# H-Bridge.net
KiCad netlist of a schematic drawn in EAGLE
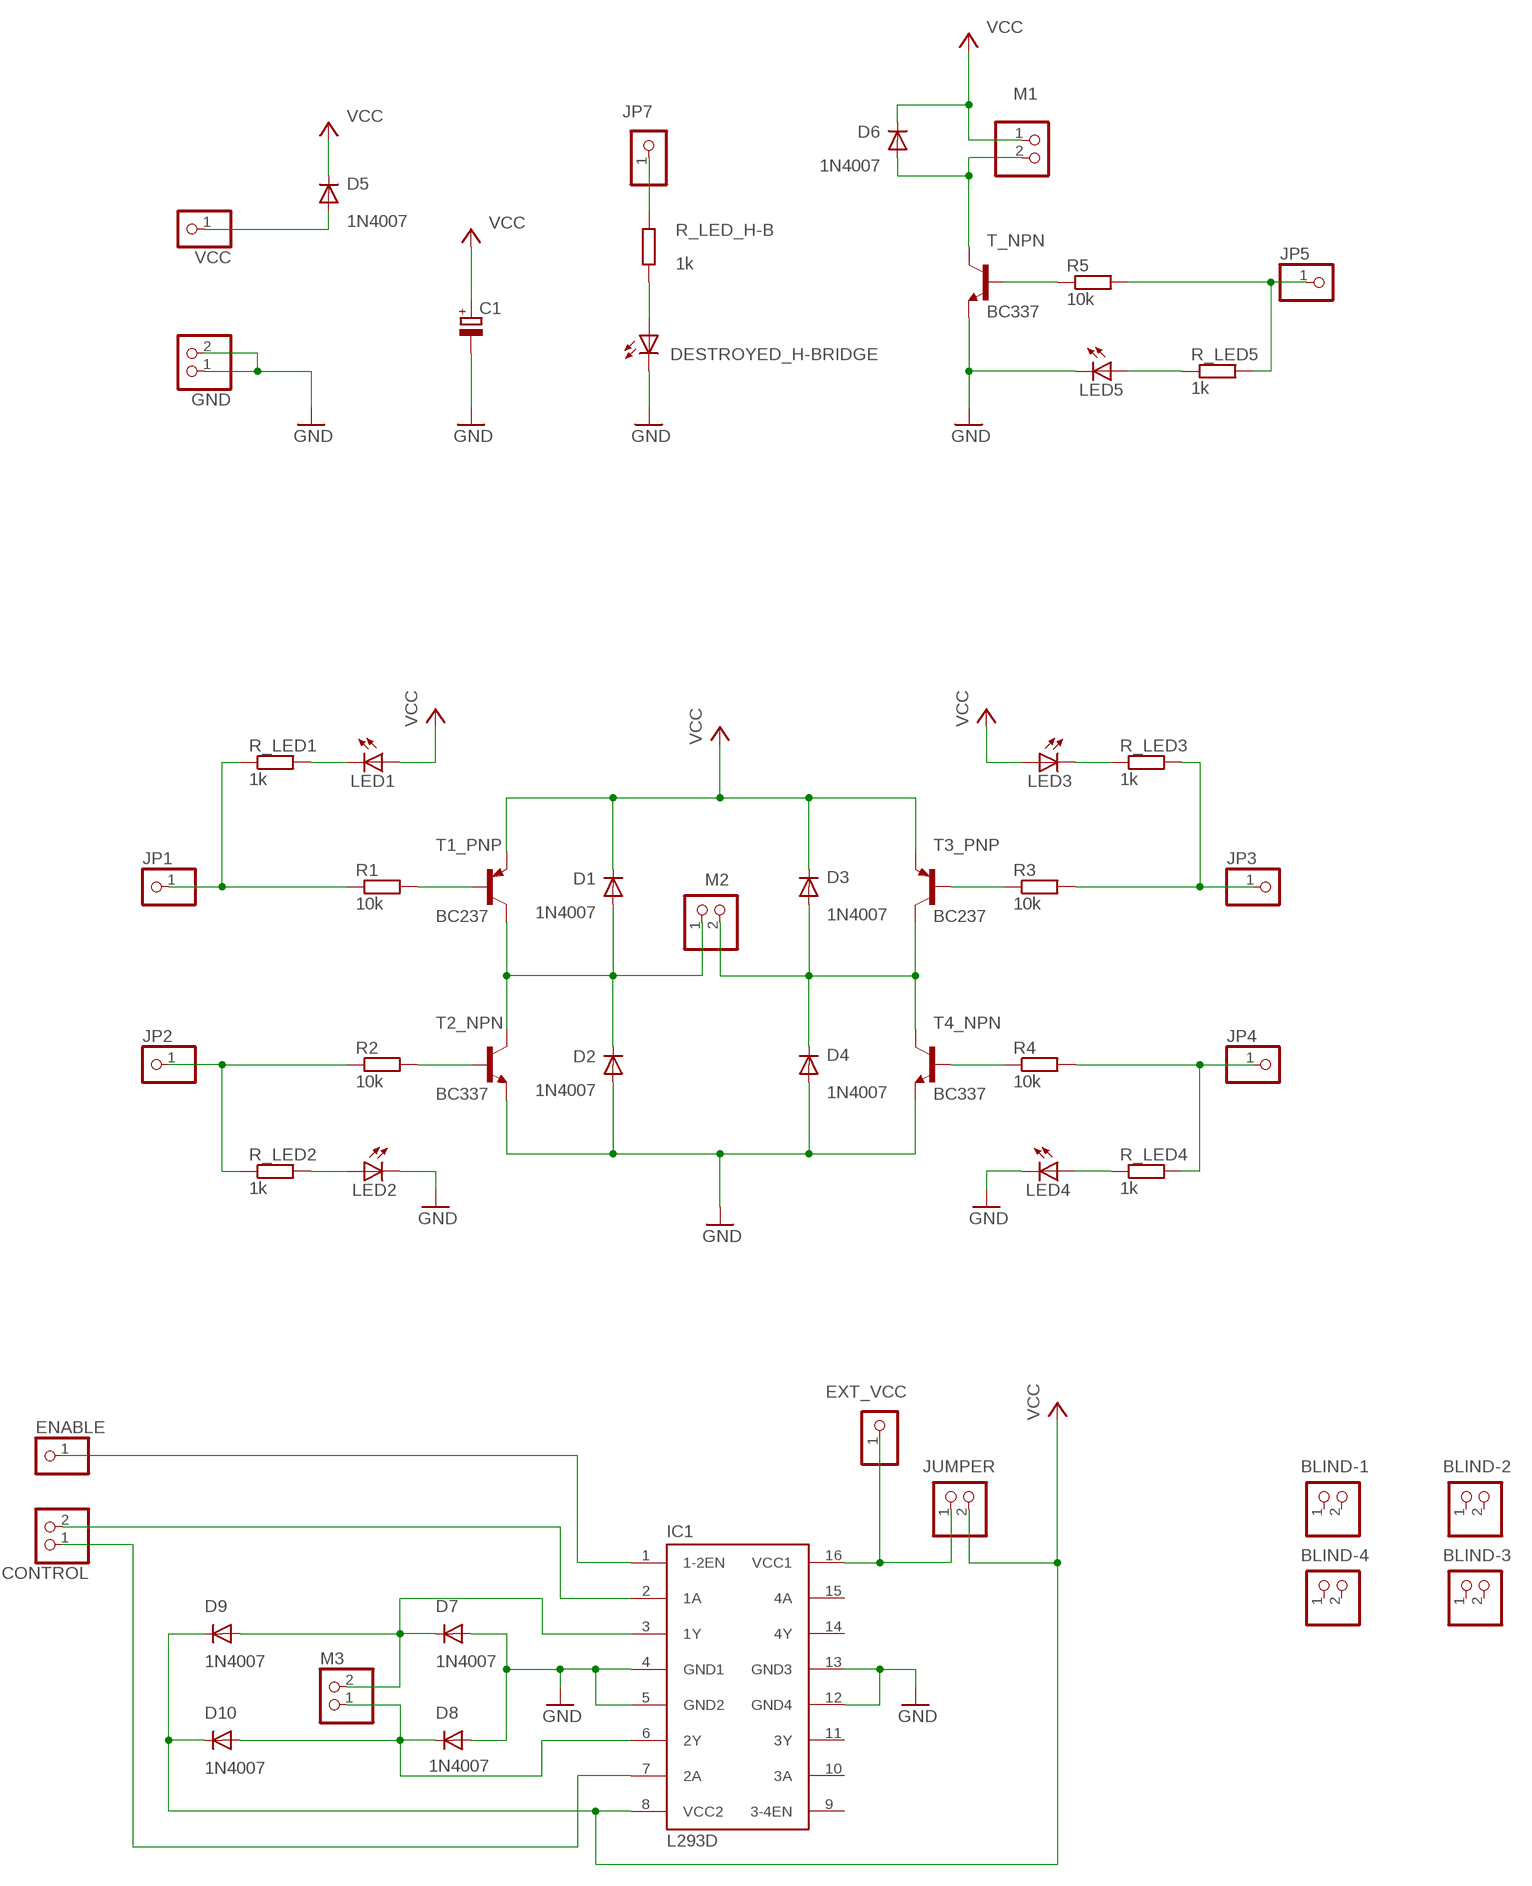
[diagram p0: schematic, sheet 1]

(export (version "E")
  (design (tool "Eeschema 10.0.6"))
  (components
    (comp (ref "BLIND-1")
      (value "PINHD-1X2")
      (footprint "eagle-import:1X02")
      (libsource (lib "eagle-import") (part "PINHD-1X2"))
    )
    (comp (ref "BLIND-2")
      (value "PINHD-1X2")
      (footprint "eagle-import:1X02")
      (libsource (lib "eagle-import") (part "PINHD-1X2"))
    )
    (comp (ref "BLIND-3")
      (value "PINHD-1X2")
      (footprint "eagle-import:1X02")
      (libsource (lib "eagle-import") (part "PINHD-1X2"))
    )
    (comp (ref "BLIND-4")
      (value "PINHD-1X2")
      (footprint "eagle-import:1X02")
      (libsource (lib "eagle-import") (part "PINHD-1X2"))
    )
    (comp (ref "C1")
      (value "CPOL-EUE2.5-7")
      (footprint "eagle-import:E2,5-7")
      (libsource (lib "eagle-import") (part "CPOL-EUE2.5-7"))
    )
    (comp (ref "CONTROL")
      (value "PINHD-1X2")
      (footprint "eagle-import:1X02")
      (libsource (lib "eagle-import") (part "PINHD-1X2"))
    )
    (comp (ref "D1")
      (value "1N4007")
      (footprint "eagle-import:DO41-10")
      (libsource (lib "eagle-import") (part "1N4004"))
    )
    (comp (ref "D2")
      (value "1N4007")
      (footprint "eagle-import:DO41-10")
      (libsource (lib "eagle-import") (part "1N4004"))
    )
    (comp (ref "D3")
      (value "1N4007")
      (footprint "eagle-import:DO41-10")
      (libsource (lib "eagle-import") (part "1N4004"))
    )
    (comp (ref "D4")
      (value "1N4007")
      (footprint "eagle-import:DO41-10")
      (libsource (lib "eagle-import") (part "1N4004"))
    )
    (comp (ref "D5")
      (value "1N4007")
      (footprint "eagle-import:DO41-10")
      (libsource (lib "eagle-import") (part "1N4004"))
    )
    (comp (ref "D6")
      (value "1N4007")
      (footprint "eagle-import:DO41-10")
      (libsource (lib "eagle-import") (part "1N4004"))
    )
    (comp (ref "D7")
      (value "1N4007")
      (footprint "eagle-import:DO41-10")
      (libsource (lib "eagle-import") (part "1N4004"))
    )
    (comp (ref "D8")
      (value "1N4007")
      (footprint "eagle-import:DO41-10")
      (libsource (lib "eagle-import") (part "1N4004"))
    )
    (comp (ref "D9")
      (value "1N4007")
      (footprint "eagle-import:DO41-10")
      (libsource (lib "eagle-import") (part "1N4004"))
    )
    (comp (ref "D10")
      (value "1N4007")
      (footprint "eagle-import:DO41-10")
      (libsource (lib "eagle-import") (part "1N4004"))
    )
    (comp (ref "DESTROYED_H-BRIDGE")
      (value "LED5MM")
      (footprint "eagle-import:LED5MM")
      (libsource (lib "eagle-import") (part "LED5MM"))
    )
    (comp (ref "ENABLE")
      (value "PINHD-1X1")
      (footprint "eagle-import:1X01")
      (libsource (lib "eagle-import") (part "PINHD-1X1"))
    )
    (comp (ref "EXT_VCC")
      (value "PINHD-1X1")
      (footprint "eagle-import:1X01")
      (libsource (lib "eagle-import") (part "PINHD-1X1"))
    )
    (comp (ref "GND")
      (value "PINHD-1X2")
      (footprint "eagle-import:1X02")
      (libsource (lib "eagle-import") (part "PINHD-1X2"))
    )
    (comp (ref "IC1")
      (value "L293D")
      (footprint "eagle-import:DIL16")
      (libsource (lib "eagle-import") (part "L293D"))
    )
    (comp (ref "JP1")
      (value "PINHD-1X1")
      (footprint "eagle-import:1X01")
      (libsource (lib "eagle-import") (part "PINHD-1X1"))
    )
    (comp (ref "JP2")
      (value "PINHD-1X1")
      (footprint "eagle-import:1X01")
      (libsource (lib "eagle-import") (part "PINHD-1X1"))
    )
    (comp (ref "JP3")
      (value "PINHD-1X1")
      (footprint "eagle-import:1X01")
      (libsource (lib "eagle-import") (part "PINHD-1X1"))
    )
    (comp (ref "JP4")
      (value "PINHD-1X1")
      (footprint "eagle-import:1X01")
      (libsource (lib "eagle-import") (part "PINHD-1X1"))
    )
    (comp (ref "JP5")
      (value "PINHD-1X1")
      (footprint "eagle-import:1X01")
      (libsource (lib "eagle-import") (part "PINHD-1X1"))
    )
    (comp (ref "JP7")
      (value "PINHD-1X1")
      (footprint "eagle-import:1X01")
      (libsource (lib "eagle-import") (part "PINHD-1X1"))
    )
    (comp (ref "JUMPER")
      (value "PINHD-1X2")
      (footprint "eagle-import:1X02")
      (libsource (lib "eagle-import") (part "PINHD-1X2"))
    )
    (comp (ref "LED1")
      (value "LED5MM")
      (footprint "eagle-import:LED5MM")
      (libsource (lib "eagle-import") (part "LED5MM"))
    )
    (comp (ref "LED2")
      (value "LED5MM")
      (footprint "eagle-import:LED5MM")
      (libsource (lib "eagle-import") (part "LED5MM"))
    )
    (comp (ref "LED3")
      (value "LED5MM")
      (footprint "eagle-import:LED5MM")
      (libsource (lib "eagle-import") (part "LED5MM"))
    )
    (comp (ref "LED4")
      (value "LED5MM")
      (footprint "eagle-import:LED5MM")
      (libsource (lib "eagle-import") (part "LED5MM"))
    )
    (comp (ref "LED5")
      (value "LED5MM")
      (footprint "eagle-import:LED5MM")
      (libsource (lib "eagle-import") (part "LED5MM"))
    )
    (comp (ref "M1")
      (value "PINHD-1X2")
      (footprint "eagle-import:1X02")
      (libsource (lib "eagle-import") (part "PINHD-1X2"))
    )
    (comp (ref "M2")
      (value "PINHD-1X2")
      (footprint "eagle-import:1X02")
      (libsource (lib "eagle-import") (part "PINHD-1X2"))
    )
    (comp (ref "M3")
      (value "PINHD-1X2")
      (footprint "eagle-import:1X02")
      (libsource (lib "eagle-import") (part "PINHD-1X2"))
    )
    (comp (ref "R1")
      (value "10k")
      (footprint "eagle-import:0207_12")
      (libsource (lib "eagle-import") (part "R-EU_0207/12"))
    )
    (comp (ref "R2")
      (value "10k")
      (footprint "eagle-import:0207_12")
      (libsource (lib "eagle-import") (part "R-EU_0207/12"))
    )
    (comp (ref "R3")
      (value "10k")
      (footprint "eagle-import:0207_12")
      (libsource (lib "eagle-import") (part "R-EU_0207/12"))
    )
    (comp (ref "R4")
      (value "10k")
      (footprint "eagle-import:0207_12")
      (libsource (lib "eagle-import") (part "R-EU_0207/12"))
    )
    (comp (ref "R5")
      (value "10k")
      (footprint "eagle-import:0207_12")
      (libsource (lib "eagle-import") (part "R-EU_0207/12"))
    )
    (comp (ref "R_LED1")
      (value "1k")
      (footprint "eagle-import:0207_12")
      (libsource (lib "eagle-import") (part "R-EU_0207/12"))
    )
    (comp (ref "R_LED2")
      (value "1k")
      (footprint "eagle-import:0207_12")
      (libsource (lib "eagle-import") (part "R-EU_0207/12"))
    )
    (comp (ref "R_LED3")
      (value "1k")
      (footprint "eagle-import:0207_12")
      (libsource (lib "eagle-import") (part "R-EU_0207/12"))
    )
    (comp (ref "R_LED4")
      (value "1k")
      (footprint "eagle-import:0207_12")
      (libsource (lib "eagle-import") (part "R-EU_0207/12"))
    )
    (comp (ref "R_LED5")
      (value "1k")
      (footprint "eagle-import:0207_12")
      (libsource (lib "eagle-import") (part "R-EU_0207/12"))
    )
    (comp (ref "R_LED_H-B")
      (value "1k")
      (footprint "eagle-import:0207_12")
      (libsource (lib "eagle-import") (part "R-EU_0207/12"))
    )
    (comp (ref "T1_PNP")
      (value "BC237")
      (footprint "eagle-import:TO92-CBE")
      (libsource (lib "eagle-import") (part "-PNP-TO92-CBE"))
    )
    (comp (ref "T2_NPN")
      (value "BC337")
      (footprint "eagle-import:TO92-CBE")
      (libsource (lib "eagle-import") (part "-NPN-TO92-CBEBC337-40"))
    )
    (comp (ref "T3_PNP")
      (value "BC237")
      (footprint "eagle-import:TO92-CBE")
      (libsource (lib "eagle-import") (part "-PNP-TO92-CBE"))
    )
    (comp (ref "T4_NPN")
      (value "BC337")
      (footprint "eagle-import:TO92-CBE")
      (libsource (lib "eagle-import") (part "-NPN-TO92-CBEBC337-40"))
    )
    (comp (ref "T_NPN")
      (value "BC337")
      (footprint "eagle-import:TO92-CBE")
      (libsource (lib "eagle-import") (part "-NPN-TO92-CBEBC337-40"))
    )
    (comp (ref "VCC")
      (value "PINHD-1X1")
      (footprint "eagle-import:1X01")
      (libsource (lib "eagle-import") (part "PINHD-1X1"))
    )
  )
  (nets
    (net (code "1") (name "GND") (class "Default")
      (node (ref "C1") (pin "-") (pinfunction "-_-") (pintype "passive"))
      (node (ref "D2") (pin "A") (pinfunction "A_A") (pintype "passive"))
      (node (ref "D4") (pin "A") (pinfunction "A_A") (pintype "passive"))
      (node (ref "D7") (pin "A") (pinfunction "A_A") (pintype "passive"))
      (node (ref "D8") (pin "A") (pinfunction "A_A") (pintype "passive"))
      (node (ref "DESTROYED_H-BRIDGE") (pin "K") (pinfunction "C_K") (pintype "passive"))
      (node (ref "GND") (pin "1") (pinfunction "1_1") (pintype "passive"))
      (node (ref "GND") (pin "2") (pinfunction "2_2") (pintype "passive"))
      (node (ref "IC1") (pin "12") (pinfunction "GND4_12") (pintype "power_in"))
      (node (ref "IC1") (pin "13") (pinfunction "GND3_13") (pintype "power_in"))
      (node (ref "IC1") (pin "4") (pinfunction "GND1_4") (pintype "power_in"))
      (node (ref "IC1") (pin "5") (pinfunction "GND2_5") (pintype "power_in"))
      (node (ref "LED2") (pin "K") (pinfunction "C_K") (pintype "passive"))
      (node (ref "LED4") (pin "K") (pinfunction "C_K") (pintype "passive"))
      (node (ref "LED5") (pin "K") (pinfunction "C_K") (pintype "passive"))
      (node (ref "T2_NPN") (pin "E") (pinfunction "E_E") (pintype "passive"))
      (node (ref "T4_NPN") (pin "E") (pinfunction "E_E") (pintype "passive"))
      (node (ref "T_NPN") (pin "E") (pinfunction "E_E") (pintype "passive"))
    )
    (net (code "2") (name "Net-(D1-PadA)") (class "Default")
      (node (ref "D1") (pin "A") (pinfunction "A_A") (pintype "passive"))
      (node (ref "D2") (pin "C") (pinfunction "C_C") (pintype "passive"))
      (node (ref "M2") (pin "1") (pinfunction "1_1") (pintype "passive"))
      (node (ref "T1_PNP") (pin "C") (pinfunction "C_C") (pintype "passive"))
      (node (ref "T2_NPN") (pin "C") (pinfunction "C_C") (pintype "passive"))
    )
    (net (code "3") (name "Net-(D3-PadA)") (class "Default")
      (node (ref "D3") (pin "A") (pinfunction "A_A") (pintype "passive"))
      (node (ref "D4") (pin "C") (pinfunction "C_C") (pintype "passive"))
      (node (ref "M2") (pin "2") (pinfunction "2_2") (pintype "passive"))
      (node (ref "T3_PNP") (pin "C") (pinfunction "C_C") (pintype "passive"))
      (node (ref "T4_NPN") (pin "C") (pinfunction "C_C") (pintype "passive"))
    )
    (net (code "4") (name "Net-(D5-PadA)") (class "Default")
      (node (ref "D5") (pin "A") (pinfunction "A_A") (pintype "passive"))
      (node (ref "VCC") (pin "1") (pinfunction "1_1") (pintype "passive"))
    )
    (net (code "5") (name "Net-(D6-PadA)") (class "Default")
      (node (ref "D6") (pin "A") (pinfunction "A_A") (pintype "passive"))
      (node (ref "M1") (pin "2") (pinfunction "2_2") (pintype "passive"))
      (node (ref "T_NPN") (pin "C") (pinfunction "C_C") (pintype "passive"))
    )
    (net (code "6") (name "Net-(DESTROYED_H-BRIDGE-PadA)") (class "Default")
      (node (ref "DESTROYED_H-BRIDGE") (pin "A") (pinfunction "A_A") (pintype "passive"))
      (node (ref "R_LED_H-B") (pin "1") (pinfunction "1_1") (pintype "passive"))
    )
    (net (code "7") (name "Net-(IC1-1-2EN)") (class "Default")
      (node (ref "ENABLE") (pin "1") (pinfunction "1_1") (pintype "passive"))
      (node (ref "IC1") (pin "1") (pinfunction "1-2EN_1") (pintype "input"))
    )
    (net (code "8") (name "Net-(IC1-1A)") (class "Default")
      (node (ref "CONTROL") (pin "2") (pinfunction "2_2") (pintype "passive"))
      (node (ref "IC1") (pin "2") (pinfunction "1A_2") (pintype "input"))
    )
    (net (code "9") (name "Net-(IC1-1Y)") (class "Default")
      (node (ref "D7") (pin "C") (pinfunction "C_C") (pintype "passive"))
      (node (ref "D9") (pin "A") (pinfunction "A_A") (pintype "passive"))
      (node (ref "IC1") (pin "3") (pinfunction "1Y_3") (pintype "output"))
      (node (ref "M3") (pin "2") (pinfunction "2_2") (pintype "passive"))
    )
    (net (code "10") (name "Net-(IC1-2A)") (class "Default")
      (node (ref "CONTROL") (pin "1") (pinfunction "1_1") (pintype "passive"))
      (node (ref "IC1") (pin "7") (pinfunction "2A_7") (pintype "input"))
    )
    (net (code "11") (name "Net-(IC1-2Y)") (class "Default")
      (node (ref "D10") (pin "A") (pinfunction "A_A") (pintype "passive"))
      (node (ref "D8") (pin "C") (pinfunction "C_C") (pintype "passive"))
      (node (ref "IC1") (pin "6") (pinfunction "2Y_6") (pintype "output"))
      (node (ref "M3") (pin "1") (pinfunction "1_1") (pintype "passive"))
    )
    (net (code "12") (name "Net-(IC1-VCC1)") (class "Default")
      (node (ref "EXT_VCC") (pin "1") (pinfunction "1_1") (pintype "passive"))
      (node (ref "IC1") (pin "16") (pinfunction "VCC1_16") (pintype "power_in"))
      (node (ref "JUMPER") (pin "1") (pinfunction "1_1") (pintype "passive"))
    )
    (net (code "13") (name "Net-(JP1-Pad1)") (class "Default")
      (node (ref "JP1") (pin "1") (pinfunction "1_1") (pintype "passive"))
      (node (ref "R1") (pin "1") (pinfunction "1_1") (pintype "passive"))
      (node (ref "R_LED1") (pin "1") (pinfunction "1_1") (pintype "passive"))
    )
    (net (code "14") (name "Net-(JP2-Pad1)") (class "Default")
      (node (ref "JP2") (pin "1") (pinfunction "1_1") (pintype "passive"))
      (node (ref "R2") (pin "1") (pinfunction "1_1") (pintype "passive"))
      (node (ref "R_LED2") (pin "1") (pinfunction "1_1") (pintype "passive"))
    )
    (net (code "15") (name "Net-(JP3-Pad1)") (class "Default")
      (node (ref "JP3") (pin "1") (pinfunction "1_1") (pintype "passive"))
      (node (ref "R3") (pin "2") (pinfunction "2_2") (pintype "passive"))
      (node (ref "R_LED3") (pin "2") (pinfunction "2_2") (pintype "passive"))
    )
    (net (code "16") (name "Net-(JP4-Pad1)") (class "Default")
      (node (ref "JP4") (pin "1") (pinfunction "1_1") (pintype "passive"))
      (node (ref "R4") (pin "2") (pinfunction "2_2") (pintype "passive"))
      (node (ref "R_LED4") (pin "2") (pinfunction "2_2") (pintype "passive"))
    )
    (net (code "17") (name "Net-(JP5-Pad1)") (class "Default")
      (node (ref "JP5") (pin "1") (pinfunction "1_1") (pintype "passive"))
      (node (ref "R5") (pin "2") (pinfunction "2_2") (pintype "passive"))
      (node (ref "R_LED5") (pin "2") (pinfunction "2_2") (pintype "passive"))
    )
    (net (code "18") (name "Net-(JP7-Pad1)") (class "Default")
      (node (ref "JP7") (pin "1") (pinfunction "1_1") (pintype "passive"))
      (node (ref "R_LED_H-B") (pin "2") (pinfunction "2_2") (pintype "passive"))
    )
    (net (code "19") (name "Net-(LED1-C)") (class "Default")
      (node (ref "LED1") (pin "K") (pinfunction "C_K") (pintype "passive"))
      (node (ref "R_LED1") (pin "2") (pinfunction "2_2") (pintype "passive"))
    )
    (net (code "20") (name "Net-(LED2-PadA)") (class "Default")
      (node (ref "LED2") (pin "A") (pinfunction "A_A") (pintype "passive"))
      (node (ref "R_LED2") (pin "2") (pinfunction "2_2") (pintype "passive"))
    )
    (net (code "21") (name "Net-(LED3-C)") (class "Default")
      (node (ref "LED3") (pin "K") (pinfunction "C_K") (pintype "passive"))
      (node (ref "R_LED3") (pin "1") (pinfunction "1_1") (pintype "passive"))
    )
    (net (code "22") (name "Net-(LED4-PadA)") (class "Default")
      (node (ref "LED4") (pin "A") (pinfunction "A_A") (pintype "passive"))
      (node (ref "R_LED4") (pin "1") (pinfunction "1_1") (pintype "passive"))
    )
    (net (code "23") (name "Net-(LED5-PadA)") (class "Default")
      (node (ref "LED5") (pin "A") (pinfunction "A_A") (pintype "passive"))
      (node (ref "R_LED5") (pin "1") (pinfunction "1_1") (pintype "passive"))
    )
    (net (code "24") (name "Net-(R1-Pad2)") (class "Default")
      (node (ref "R1") (pin "2") (pinfunction "2_2") (pintype "passive"))
      (node (ref "T1_PNP") (pin "B") (pinfunction "B_B") (pintype "passive"))
    )
    (net (code "25") (name "Net-(R2-Pad2)") (class "Default")
      (node (ref "R2") (pin "2") (pinfunction "2_2") (pintype "passive"))
      (node (ref "T2_NPN") (pin "B") (pinfunction "B_B") (pintype "passive"))
    )
    (net (code "26") (name "Net-(R3-Pad1)") (class "Default")
      (node (ref "R3") (pin "1") (pinfunction "1_1") (pintype "passive"))
      (node (ref "T3_PNP") (pin "B") (pinfunction "B_B") (pintype "passive"))
    )
    (net (code "27") (name "Net-(R4-Pad1)") (class "Default")
      (node (ref "R4") (pin "1") (pinfunction "1_1") (pintype "passive"))
      (node (ref "T4_NPN") (pin "B") (pinfunction "B_B") (pintype "passive"))
    )
    (net (code "28") (name "Net-(R5-Pad1)") (class "Default")
      (node (ref "R5") (pin "1") (pinfunction "1_1") (pintype "passive"))
      (node (ref "T_NPN") (pin "B") (pinfunction "B_B") (pintype "passive"))
    )
    (net (code "29") (name "VCC") (class "Default")
      (node (ref "C1") (pin "+") (pinfunction "+_+") (pintype "passive"))
      (node (ref "D1") (pin "C") (pinfunction "C_C") (pintype "passive"))
      (node (ref "D10") (pin "C") (pinfunction "C_C") (pintype "passive"))
      (node (ref "D3") (pin "C") (pinfunction "C_C") (pintype "passive"))
      (node (ref "D5") (pin "C") (pinfunction "C_C") (pintype "passive"))
      (node (ref "D6") (pin "C") (pinfunction "C_C") (pintype "passive"))
      (node (ref "D9") (pin "C") (pinfunction "C_C") (pintype "passive"))
      (node (ref "IC1") (pin "8") (pinfunction "VCC2_8") (pintype "power_in"))
      (node (ref "JUMPER") (pin "2") (pinfunction "2_2") (pintype "passive"))
      (node (ref "LED1") (pin "A") (pinfunction "A_A") (pintype "passive"))
      (node (ref "LED3") (pin "A") (pinfunction "A_A") (pintype "passive"))
      (node (ref "M1") (pin "1") (pinfunction "1_1") (pintype "passive"))
      (node (ref "T1_PNP") (pin "E") (pinfunction "E_E") (pintype "passive"))
      (node (ref "T3_PNP") (pin "E") (pinfunction "E_E") (pintype "passive"))
    )
    (net (code "30") (name "unconnected-(BLIND-1-Pad1)") (class "Default")
      (node (ref "BLIND-1") (pin "1") (pinfunction "1_1") (pintype "passive"))
    )
    (net (code "31") (name "unconnected-(BLIND-1-Pad2)") (class "Default")
      (node (ref "BLIND-1") (pin "2") (pinfunction "2_2") (pintype "passive"))
    )
    (net (code "32") (name "unconnected-(BLIND-2-Pad1)") (class "Default")
      (node (ref "BLIND-2") (pin "1") (pinfunction "1_1") (pintype "passive"))
    )
    (net (code "33") (name "unconnected-(BLIND-2-Pad2)") (class "Default")
      (node (ref "BLIND-2") (pin "2") (pinfunction "2_2") (pintype "passive"))
    )
    (net (code "34") (name "unconnected-(BLIND-3-Pad1)") (class "Default")
      (node (ref "BLIND-3") (pin "1") (pinfunction "1_1") (pintype "passive"))
    )
    (net (code "35") (name "unconnected-(BLIND-3-Pad2)") (class "Default")
      (node (ref "BLIND-3") (pin "2") (pinfunction "2_2") (pintype "passive"))
    )
    (net (code "36") (name "unconnected-(BLIND-4-Pad1)") (class "Default")
      (node (ref "BLIND-4") (pin "1") (pinfunction "1_1") (pintype "passive"))
    )
    (net (code "37") (name "unconnected-(BLIND-4-Pad2)") (class "Default")
      (node (ref "BLIND-4") (pin "2") (pinfunction "2_2") (pintype "passive"))
    )
    (net (code "38") (name "unconnected-(IC1-3-4EN-Pad9)") (class "Default")
      (node (ref "IC1") (pin "9") (pinfunction "3-4EN_9") (pintype "input"))
    )
    (net (code "39") (name "unconnected-(IC1-3A-Pad10)") (class "Default")
      (node (ref "IC1") (pin "10") (pinfunction "3A_10") (pintype "input"))
    )
    (net (code "40") (name "unconnected-(IC1-3Y-Pad11)") (class "Default")
      (node (ref "IC1") (pin "11") (pinfunction "3Y_11") (pintype "output"))
    )
    (net (code "41") (name "unconnected-(IC1-4A-Pad15)") (class "Default")
      (node (ref "IC1") (pin "15") (pinfunction "4A_15") (pintype "input"))
    )
    (net (code "42") (name "unconnected-(IC1-4Y-Pad14)") (class "Default")
      (node (ref "IC1") (pin "14") (pinfunction "4Y_14") (pintype "output"))
    )
  )
)
